# Power.net
KiCad netlist of a schematic drawn in Altium Designer
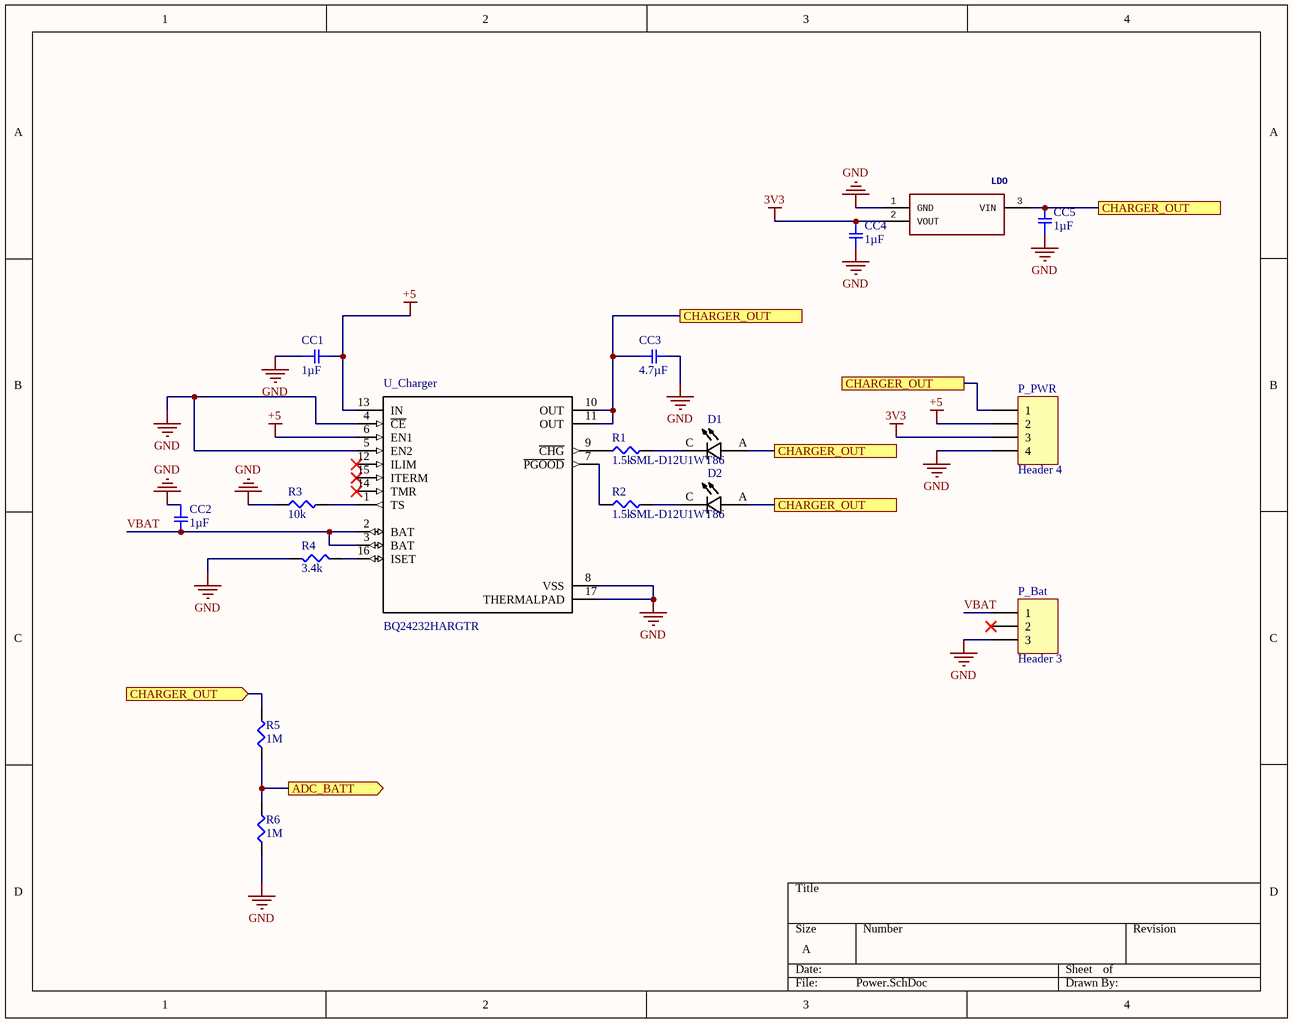
[diagram p0: Power.SchDoc]

(export (version "E")
  (design (tool "Eeschema 10.0.6"))
  (components
    (comp (ref "CC1")
      (value "1µF")
      (footprint "SMD-0603C")
      (description "CAP CER 1UF 10V X5R 0603")
      (fields
        (field (name "DIGI-KEY PART NUMBER") "490-1543-1-ND")
        (field (name "PART NUMBER") "GRM188R61A105KA61D")
      )
      (libsource (lib "capacitor_murata_0603") (part "GRM188R61A105KA61D"))
    )
    (comp (ref "CC2")
      (value "1µF")
      (footprint "SMD-0603C")
      (description "CAP CER 1UF 10V X5R 0603")
      (fields
        (field (name "DIGI-KEY PART NUMBER") "490-1543-1-ND")
        (field (name "PART NUMBER") "GRM188R61A105KA61D")
      )
      (libsource (lib "capacitor_murata_0603") (part "GRM188R61A105KA61D"))
    )
    (comp (ref "CC3")
      (value "4.7µF")
      (footprint "SMD-0603C")
      (description "CAP CER 4.7UF 4V X5R 0603")
      (fields
        (field (name "DIGI-KEY PART NUMBER") "490-3891-1-ND")
        (field (name "PART NUMBER") "GRM185R60G475ME15D")
      )
      (libsource (lib "capacitor_murata_0603") (part "GRM185R60G475ME15D"))
    )
    (comp (ref "CC4")
      (value "1µF")
      (footprint "SMD-0603C")
      (description "CAP CER 1UF 10V X5R 0603")
      (fields
        (field (name "DIGI-KEY PART NUMBER") "490-1543-1-ND")
        (field (name "PART NUMBER") "GRM188R61A105KA61D")
      )
      (libsource (lib "capacitor_murata_0603") (part "GRM188R61A105KA61D"))
    )
    (comp (ref "CC5")
      (value "1µF")
      (footprint "SMD-0603C")
      (description "CAP CER 1UF 10V X5R 0603")
      (fields
        (field (name "DIGI-KEY PART NUMBER") "490-1543-1-ND")
        (field (name "PART NUMBER") "GRM188R61A105KA61D")
      )
      (libsource (lib "capacitor_murata_0603") (part "GRM188R61A105KA61D"))
    )
    (comp (ref "D1")
      (value "SML-D12U1WT86")
      (footprint "*LED_SML-D12Y1WT86_SML-D12U1WT86(Primary)")
      (description "SML-D12 Series Red 0603 Diffused 63 mcd 2.2 V Surface Mount LED")
      (fields (field (name "DIGI-KEY_PART_NUMBER") "SML-D12U1WT86CT-ND") (field (name "MF") "Rohm"))
      (libsource (lib "SML-D12U1WT86") (part "SML-D12U1WT86"))
    )
    (comp (ref "D2")
      (value "SML-D12U1WT86")
      (footprint "*LED_SML-D12Y1WT86_SML-D12U1WT86(Primary)")
      (description "SML-D12 Series Red 0603 Diffused 63 mcd 2.2 V Surface Mount LED")
      (fields (field (name "DIGI-KEY_PART_NUMBER") "SML-D12U1WT86CT-ND") (field (name "MF") "Rohm"))
      (libsource (lib "SML-D12U1WT86") (part "SML-D12U1WT86"))
    )
    (comp (ref "LDO")
      (value "250mA 3.3V Ultra Low IQ LDO Reg. SOT23 DiodesZetex AP2138N-3.3TRG1, Low Noise LDO Voltage Regulator, 250 (Min)mA, 3.3 V +/-2%, 2.5 to 6.6 Vin, 3-Pin SOT-23Source:  Datasheet")
      (footprint "SOT95P282X145-3N")
      (fields
        (field (name "MANUFACTURER_PART_NUMBER") "AP2138N-3.3TRG1")
        (field (name "MOUSER_PART_NUMBER") "621-AP2138N-3.3TRG1")
        (field (name "RS_PART_NUMBER") "9210398P")
      )
      (libsource (lib "AP2138N-3.3TRG1") (part "AP2138N-3.3TRG1"))
    )
    (comp (ref "P_Bat")
      (value "Header 3")
      (footprint "HDR1X3")
      (description "Header, 3-Pin")
      (fields (field (name "PUBLISHER") "Altium Limited"))
      (libsource (lib "Miscellaneous Connectors") (part "Header 3"))
    )
    (comp (ref "P_PWR")
      (value "Header 4")
      (footprint "HDR1X4")
      (description "Header, 4-Pin")
      (fields (field (name "PUBLISHER") "Altium Limited"))
      (libsource (lib "Miscellaneous Connectors") (part "Header 4"))
    )
    (comp (ref "R1")
      (value "1.5k")
      (footprint "SMD-0603-RES")
      (description "RES SMD 1.5K OHM 1% 1/10W 0603")
      (fields
        (field (name "PART NUMBER") "ERJ-3EKF1501V")
        (field (name "DIGI-KEY PART NUMBER") "P1.50KHCT-ND")
      )
      (libsource (lib "Panasonic_ERJ_0603") (part "ERJ-3EKF1501V"))
    )
    (comp (ref "R2")
      (value "1.5k")
      (footprint "SMD-0603-RES")
      (description "RES SMD 1.5K OHM 1% 1/10W 0603")
      (fields
        (field (name "PART NUMBER") "ERJ-3EKF1501V")
        (field (name "DIGI-KEY PART NUMBER") "P1.50KHCT-ND")
      )
      (libsource (lib "Panasonic_ERJ_0603") (part "ERJ-3EKF1501V"))
    )
    (comp (ref "R3")
      (value "10k")
      (footprint "SMD-0603-RES")
      (description "RES SMD 10K OHM 5% 1/4W 0603")
      (fields (field (name "PART NUMBER") "ERJ-PA3J103V") (field (name "DIGI-KEY PART NUMBER") "P10KBZCT-ND"))
      (libsource (lib "Panasonic_ERJ_0603") (part "ERJ-PA3J103V"))
    )
    (comp (ref "R4")
      (value "3.4k")
      (footprint "SMD-0603-RES")
      (description "RES SMD 3.4K OHM 1% 1/10W 0603")
      (fields
        (field (name "PART NUMBER") "ERJ-3EKF3401V")
        (field (name "DIGI-KEY PART NUMBER") "P3.40KHCT-ND")
      )
      (libsource (lib "Panasonic_ERJ_0603") (part "ERJ-3EKF3401V"))
    )
    (comp (ref "R5")
      (value "1M")
      (footprint "SMD-0603-RES")
      (description "RES SMD 1M OHM 1% 1/10W 0603")
      (fields
        (field (name "PART NUMBER") "ERJ-3EKF1004V")
        (field (name "DIGI-KEY PART NUMBER") "P1.00MHCT-ND")
      )
      (libsource (lib "Panasonic_ERJ_0603") (part "ERJ-3EKF1004V"))
    )
    (comp (ref "R6")
      (value "1M")
      (footprint "SMD-0603-RES")
      (description "RES SMD 1M OHM 1% 1/10W 0603")
      (fields
        (field (name "PART NUMBER") "ERJ-3EKF1004V")
        (field (name "DIGI-KEY PART NUMBER") "P1.00MHCT-ND")
      )
      (libsource (lib "Panasonic_ERJ_0603") (part "ERJ-3EKF1004V"))
    )
    (comp (ref "U_Charger")
      (value "BQ24232HARGTR")
      (footprint "*QFN50P300X300X100-17N")
      (fields (field (name "MF") "Texas Instruments") (field (name "DIGI-KEY_PART_NUMBER") "296-49554-1-ND"))
      (libsource (lib "BQ24232HARGTR") (part "BQ24232HARGTR"))
    )
  )
  (nets
    (net (code "1") (name "+5") (class "Default")
      (node (ref "CC1") (pin "2") (pinfunction "2_2") (pintype "passive"))
      (node (ref "P_PWR") (pin "2") (pinfunction "2_2") (pintype "passive"))
      (node (ref "U_Charger") (pin "13") (pinfunction "IN_13") (pintype "power_in"))
      (node (ref "U_Charger") (pin "6") (pinfunction "EN1_6") (pintype "input"))
    )
    (net (code "2") (name "/ADC_BATT") (class "Default")
      (node (ref "R5") (pin "1") (pinfunction "1_1") (pintype "passive"))
      (node (ref "R6") (pin "2") (pinfunction "2_2") (pintype "passive"))
    )
    (net (code "3") (name "/CHARGER_OUT") (class "Default")
      (node (ref "CC3") (pin "1") (pinfunction "1_1") (pintype "passive"))
      (node (ref "CC5") (pin "2") (pinfunction "2_2") (pintype "passive"))
      (node (ref "D1") (pin "A") (pinfunction "A_A") (pintype "passive"))
      (node (ref "D2") (pin "A") (pinfunction "A_A") (pintype "passive"))
      (node (ref "LDO") (pin "3") (pinfunction "VIN_3") (pintype "power_in"))
      (node (ref "P_PWR") (pin "1") (pinfunction "1_1") (pintype "passive"))
      (node (ref "R5") (pin "2") (pinfunction "2_2") (pintype "passive"))
      (node (ref "U_Charger") (pin "10") (pinfunction "OUT_10") (pintype "power_in"))
      (node (ref "U_Charger") (pin "11") (pinfunction "OUT_11") (pintype "power_in"))
    )
    (net (code "4") (name "/VBAT") (class "Default")
      (node (ref "CC2") (pin "2") (pinfunction "2_2") (pintype "passive"))
      (node (ref "P_Bat") (pin "1") (pinfunction "1_1") (pintype "passive"))
      (node (ref "U_Charger") (pin "2") (pinfunction "BAT_2") (pintype "bidirectional"))
      (node (ref "U_Charger") (pin "3") (pinfunction "BAT_3") (pintype "bidirectional"))
    )
    (net (code "5") (name "3V3") (class "Default")
      (node (ref "CC4") (pin "1") (pinfunction "1_1") (pintype "passive"))
      (node (ref "LDO") (pin "2") (pinfunction "VOUT_2") (pintype "power_in"))
      (node (ref "P_PWR") (pin "3") (pinfunction "3_3") (pintype "passive"))
    )
    (net (code "6") (name "GND") (class "Default")
      (node (ref "CC1") (pin "1") (pinfunction "1_1") (pintype "passive"))
      (node (ref "CC2") (pin "1") (pinfunction "1_1") (pintype "passive"))
      (node (ref "CC3") (pin "2") (pinfunction "2_2") (pintype "passive"))
      (node (ref "CC4") (pin "2") (pinfunction "2_2") (pintype "passive"))
      (node (ref "CC5") (pin "1") (pinfunction "1_1") (pintype "passive"))
      (node (ref "LDO") (pin "1") (pinfunction "GND_1") (pintype "power_in"))
      (node (ref "P_Bat") (pin "3") (pinfunction "3_3") (pintype "passive"))
      (node (ref "P_PWR") (pin "4") (pinfunction "4_4") (pintype "passive"))
      (node (ref "R3") (pin "1") (pinfunction "1_1") (pintype "passive"))
      (node (ref "R4") (pin "2") (pinfunction "2_2") (pintype "passive"))
      (node (ref "R6") (pin "1") (pinfunction "1_1") (pintype "passive"))
      (node (ref "U_Charger") (pin "17") (pinfunction "THERMALPAD_17") (pintype "power_in"))
      (node (ref "U_Charger") (pin "4") (pinfunction "~{CE}_4") (pintype "input"))
      (node (ref "U_Charger") (pin "5") (pinfunction "EN2_5") (pintype "input"))
      (node (ref "U_Charger") (pin "8") (pinfunction "VSS_8") (pintype "power_in"))
    )
    (net (code "7") (name "Net-(D1-PadC)") (class "Default")
      (node (ref "D1") (pin "C") (pinfunction "C_C") (pintype "passive"))
      (node (ref "R1") (pin "2") (pinfunction "2_2") (pintype "passive"))
    )
    (net (code "8") (name "Net-(D2-PadC)") (class "Default")
      (node (ref "D2") (pin "C") (pinfunction "C_C") (pintype "passive"))
      (node (ref "R2") (pin "2") (pinfunction "2_2") (pintype "passive"))
    )
    (net (code "9") (name "Net-(U_Charger-ISET)") (class "Default")
      (node (ref "R4") (pin "1") (pinfunction "1_1") (pintype "passive"))
      (node (ref "U_Charger") (pin "16") (pinfunction "ISET_16") (pintype "bidirectional"))
    )
    (net (code "10") (name "Net-(U_Charger-TS)") (class "Default")
      (node (ref "R3") (pin "2") (pinfunction "2_2") (pintype "passive"))
      (node (ref "U_Charger") (pin "1") (pinfunction "TS_1") (pintype "output"))
    )
    (net (code "11") (name "Net-(U_Charger-~{CHG})") (class "Default")
      (node (ref "R1") (pin "1") (pinfunction "1_1") (pintype "passive"))
      (node (ref "U_Charger") (pin "9") (pinfunction "~{CHG}_9") (pintype "output"))
    )
    (net (code "12") (name "Net-(U_Charger-~{PGOOD})") (class "Default")
      (node (ref "R2") (pin "1") (pinfunction "1_1") (pintype "passive"))
      (node (ref "U_Charger") (pin "7") (pinfunction "~{PGOOD}_7") (pintype "output"))
    )
    (net (code "13") (name "unconnected-(P_Bat-Pad2)") (class "Default")
      (node (ref "P_Bat") (pin "2") (pinfunction "2_2") (pintype "passive+no_connect"))
    )
    (net (code "14") (name "unconnected-(U_Charger-ILIM-Pad12)") (class "Default")
      (node (ref "U_Charger") (pin "12") (pinfunction "ILIM_12") (pintype "input+no_connect"))
    )
    (net (code "15") (name "unconnected-(U_Charger-ITERM-Pad15)") (class "Default")
      (node (ref "U_Charger") (pin "15") (pinfunction "ITERM_15") (pintype "input+no_connect"))
    )
    (net (code "16") (name "unconnected-(U_Charger-TMR-Pad14)") (class "Default")
      (node (ref "U_Charger") (pin "14") (pinfunction "TMR_14") (pintype "input+no_connect"))
    )
  )
)
